# 13_LMS3_Power.net
KiCad netlist of a schematic drawn in Altium Designer
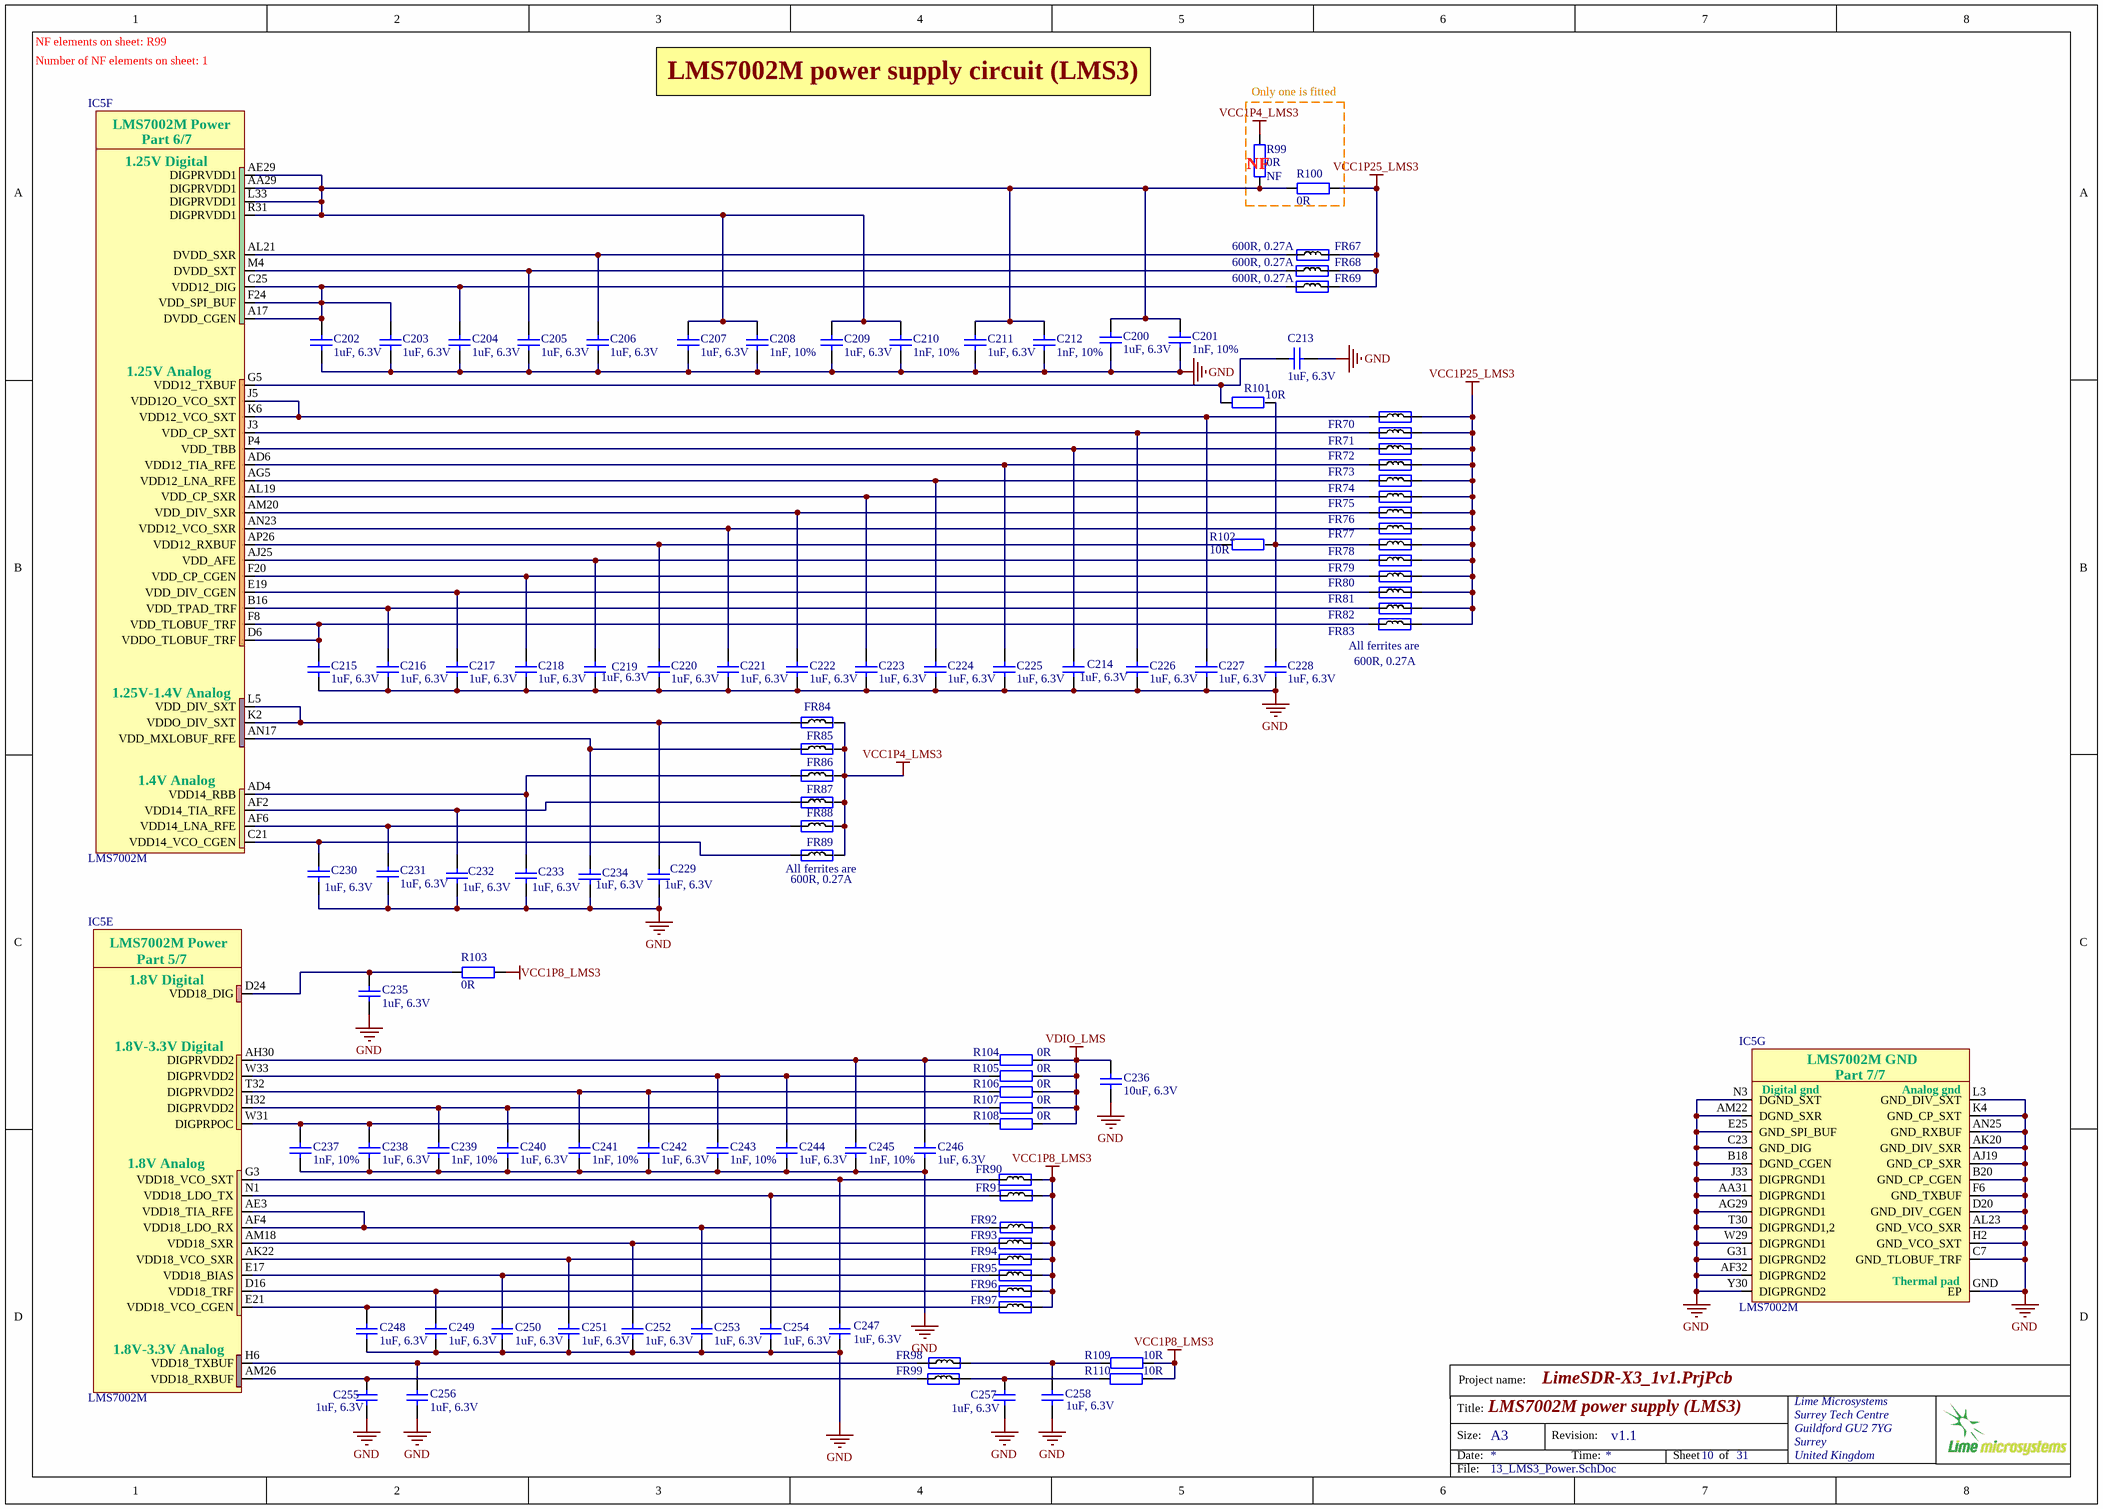
[diagram p0: 13_LMS3_Power.SchDoc]

(export (version "E")
  (design (tool "Eeschema 10.0.6"))
  (components
    (comp (ref "C200")
      (value "1uF, 6.3V")
      (footprint "CAP0201")
      (fields (field (name "TOLERANCE") "±20%") (field (name "MANUFACTURER") "TDK Corporation"))
      (libsource (lib "") (part "Cap_0402_1"))
    )
    (comp (ref "C201")
      (value "1nF, 10%")
      (footprint "CAP0201")
      (fields (field (name "TOLERANCE") "±10%") (field (name "MANUFACTURER") "TDK Corporation"))
      (libsource (lib "") (part "Cap_0402_1"))
    )
    (comp (ref "C202")
      (value "1uF, 6.3V")
      (footprint "CAP0201")
      (fields (field (name "TOLERANCE") "±20%") (field (name "MANUFACTURER") "TDK Corporation"))
      (libsource (lib "") (part "Cap_0402_2"))
    )
    (comp (ref "C203")
      (value "1uF, 6.3V")
      (footprint "CAP0201")
      (fields (field (name "TOLERANCE") "±20%") (field (name "MANUFACTURER") "TDK Corporation"))
      (libsource (lib "") (part "Cap_0402_2"))
    )
    (comp (ref "C204")
      (value "1uF, 6.3V")
      (footprint "CAP0201")
      (fields (field (name "TOLERANCE") "±20%") (field (name "MANUFACTURER") "TDK Corporation"))
      (libsource (lib "") (part "Cap_0402_2"))
    )
    (comp (ref "C205")
      (value "1uF, 6.3V")
      (footprint "CAP0201")
      (fields (field (name "TOLERANCE") "±20%") (field (name "MANUFACTURER") "TDK Corporation"))
      (libsource (lib "") (part "Cap_0402_1"))
    )
    (comp (ref "C206")
      (value "1uF, 6.3V")
      (footprint "CAP0201")
      (fields (field (name "TOLERANCE") "±20%") (field (name "MANUFACTURER") "TDK Corporation"))
      (libsource (lib "") (part "Cap_0402_2"))
    )
    (comp (ref "C207")
      (value "1uF, 6.3V")
      (footprint "CAP0201")
      (fields (field (name "TOLERANCE") "±20%") (field (name "MANUFACTURER") "TDK Corporation"))
      (libsource (lib "") (part "Cap_0402_1"))
    )
    (comp (ref "C208")
      (value "1nF, 10%")
      (footprint "CAP0201")
      (fields (field (name "TOLERANCE") "±10%") (field (name "MANUFACTURER") "TDK Corporation"))
      (libsource (lib "") (part "Cap_0402_1"))
    )
    (comp (ref "C209")
      (value "1uF, 6.3V")
      (footprint "CAP0201")
      (fields (field (name "TOLERANCE") "±20%") (field (name "MANUFACTURER") "TDK Corporation"))
      (libsource (lib "") (part "Cap_0402_1"))
    )
    (comp (ref "C210")
      (value "1nF, 10%")
      (footprint "CAP0201")
      (fields (field (name "TOLERANCE") "±10%") (field (name "MANUFACTURER") "TDK Corporation"))
      (libsource (lib "") (part "Cap_0402_1"))
    )
    (comp (ref "C211")
      (value "1uF, 6.3V")
      (footprint "CAP0201")
      (fields (field (name "TOLERANCE") "±20%") (field (name "MANUFACTURER") "TDK Corporation"))
      (libsource (lib "") (part "Cap_0402_1"))
    )
    (comp (ref "C212")
      (value "1nF, 10%")
      (footprint "CAP0201")
      (fields (field (name "TOLERANCE") "±10%") (field (name "MANUFACTURER") "TDK Corporation"))
      (libsource (lib "") (part "Cap_0402_1"))
    )
    (comp (ref "C213")
      (value "1uF, 6.3V")
      (footprint "CAP0201")
      (fields (field (name "TOLERANCE") "±20%") (field (name "MANUFACTURER") "TDK Corporation"))
      (libsource (lib "") (part "Cap_0402_4"))
    )
    (comp (ref "C214")
      (value "1uF, 6.3V")
      (footprint "CAP0201")
      (fields (field (name "TOLERANCE") "±20%") (field (name "MANUFACTURER") "TDK Corporation"))
      (libsource (lib "") (part "Cap_0402_2"))
    )
    (comp (ref "C215")
      (value "1uF, 6.3V")
      (footprint "CAP0201")
      (fields (field (name "TOLERANCE") "±20%") (field (name "MANUFACTURER") "TDK Corporation"))
      (libsource (lib "") (part "Cap_0402_2"))
    )
    (comp (ref "C216")
      (value "1uF, 6.3V")
      (footprint "CAP0201")
      (fields (field (name "TOLERANCE") "±20%") (field (name "MANUFACTURER") "TDK Corporation"))
      (libsource (lib "") (part "Cap_0402_2"))
    )
    (comp (ref "C217")
      (value "1uF, 6.3V")
      (footprint "CAP0201")
      (fields (field (name "TOLERANCE") "±20%") (field (name "MANUFACTURER") "TDK Corporation"))
      (libsource (lib "") (part "Cap_0402_2"))
    )
    (comp (ref "C218")
      (value "1uF, 6.3V")
      (footprint "CAP0201")
      (fields (field (name "TOLERANCE") "±20%") (field (name "MANUFACTURER") "TDK Corporation"))
      (libsource (lib "") (part "Cap_0402_1"))
    )
    (comp (ref "C219")
      (value "1uF, 6.3V")
      (footprint "CAP0201")
      (fields (field (name "TOLERANCE") "±20%") (field (name "MANUFACTURER") "TDK Corporation"))
      (libsource (lib "") (part "Cap_0402_2"))
    )
    (comp (ref "C220")
      (value "1uF, 6.3V")
      (footprint "CAP0201")
      (fields (field (name "TOLERANCE") "±20%") (field (name "MANUFACTURER") "TDK Corporation"))
      (libsource (lib "") (part "Cap_0402_2"))
    )
    (comp (ref "C221")
      (value "1uF, 6.3V")
      (footprint "CAP0201")
      (fields (field (name "TOLERANCE") "±20%") (field (name "MANUFACTURER") "TDK Corporation"))
      (libsource (lib "") (part "Cap_0402_2"))
    )
    (comp (ref "C222")
      (value "1uF, 6.3V")
      (footprint "CAP0201")
      (fields (field (name "TOLERANCE") "±20%") (field (name "MANUFACTURER") "TDK Corporation"))
      (libsource (lib "") (part "Cap_0402_2"))
    )
    (comp (ref "C223")
      (value "1uF, 6.3V")
      (footprint "CAP0201")
      (fields (field (name "TOLERANCE") "±20%") (field (name "MANUFACTURER") "TDK Corporation"))
      (libsource (lib "") (part "Cap_0402_2"))
    )
    (comp (ref "C224")
      (value "1uF, 6.3V")
      (footprint "CAP0201")
      (fields (field (name "TOLERANCE") "±20%") (field (name "MANUFACTURER") "TDK Corporation"))
      (libsource (lib "") (part "Cap_0402_2"))
    )
    (comp (ref "C225")
      (value "1uF, 6.3V")
      (footprint "CAP0201")
      (fields (field (name "TOLERANCE") "±20%") (field (name "MANUFACTURER") "TDK Corporation"))
      (libsource (lib "") (part "Cap_0402_1"))
    )
    (comp (ref "C226")
      (value "1uF, 6.3V")
      (footprint "CAP0201")
      (fields (field (name "TOLERANCE") "±20%") (field (name "MANUFACTURER") "TDK Corporation"))
      (libsource (lib "") (part "Cap_0402_2"))
    )
    (comp (ref "C227")
      (value "1uF, 6.3V")
      (footprint "CAP0201")
      (fields (field (name "TOLERANCE") "±20%") (field (name "MANUFACTURER") "TDK Corporation"))
      (libsource (lib "") (part "Cap_0402_1"))
    )
    (comp (ref "C228")
      (value "1uF, 6.3V")
      (footprint "CAP0201")
      (fields (field (name "TOLERANCE") "±20%") (field (name "MANUFACTURER") "TDK Corporation"))
      (libsource (lib "") (part "Cap_0402_1"))
    )
    (comp (ref "C229")
      (value "1uF, 6.3V")
      (footprint "CAP0201")
      (fields (field (name "TOLERANCE") "±20%") (field (name "MANUFACTURER") "TDK Corporation"))
      (libsource (lib "") (part "Cap_0402_2"))
    )
    (comp (ref "C230")
      (value "1uF, 6.3V")
      (footprint "CAP0201")
      (fields (field (name "TOLERANCE") "±20%") (field (name "MANUFACTURER") "TDK Corporation"))
      (libsource (lib "") (part "Cap_0402_2"))
    )
    (comp (ref "C231")
      (value "1uF, 6.3V")
      (footprint "CAP0201")
      (fields (field (name "TOLERANCE") "±20%") (field (name "MANUFACTURER") "TDK Corporation"))
      (libsource (lib "") (part "Cap_0402_2"))
    )
    (comp (ref "C232")
      (value "1uF, 6.3V")
      (footprint "CAP0201")
      (fields (field (name "TOLERANCE") "±20%") (field (name "MANUFACTURER") "TDK Corporation"))
      (libsource (lib "") (part "Cap_0402_3"))
    )
    (comp (ref "C233")
      (value "1uF, 6.3V")
      (footprint "CAP0201")
      (fields (field (name "TOLERANCE") "±20%") (field (name "MANUFACTURER") "TDK Corporation"))
      (libsource (lib "") (part "Cap_0402_3"))
    )
    (comp (ref "C234")
      (value "1uF, 6.3V")
      (footprint "CAP0201")
      (fields (field (name "TOLERANCE") "±20%") (field (name "MANUFACTURER") "TDK Corporation"))
      (libsource (lib "") (part "Cap_0402_2"))
    )
    (comp (ref "C235")
      (value "1uF, 6.3V")
      (footprint "CAP0201")
      (fields (field (name "TOLERANCE") "±20%") (field (name "MANUFACTURER") "TDK Corporation"))
      (libsource (lib "LimeMicroAltiumLib_schLib") (part "Cap_0402"))
    )
    (comp (ref "C236")
      (value "10uF, 6.3V")
      (footprint "CAP0603")
      (fields (field (name "TOLERANCE") "±20%") (field (name "MANUFACTURER") "Yageo"))
      (libsource (lib "LimeFPGAboard_schLib") (part "Cap_0603"))
    )
    (comp (ref "C237")
      (value "1nF, 10%")
      (footprint "CAP0201")
      (fields (field (name "TOLERANCE") "±10%") (field (name "MANUFACTURER") "TDK Corporation"))
      (libsource (lib "LimeMicroAltiumLib_schLib") (part "Cap_0402"))
    )
    (comp (ref "C238")
      (value "1uF, 6.3V")
      (footprint "CAP0201")
      (fields (field (name "TOLERANCE") "±20%") (field (name "MANUFACTURER") "TDK Corporation"))
      (libsource (lib "LimeMicroAltiumLib_schLib") (part "Cap_0402"))
    )
    (comp (ref "C239")
      (value "1nF, 10%")
      (footprint "CAP0201")
      (fields (field (name "TOLERANCE") "±10%") (field (name "MANUFACTURER") "TDK Corporation"))
      (libsource (lib "LimeMicroAltiumLib_schLib") (part "Cap_0402"))
    )
    (comp (ref "C240")
      (value "1uF, 6.3V")
      (footprint "CAP0201")
      (fields (field (name "TOLERANCE") "±20%") (field (name "MANUFACTURER") "TDK Corporation"))
      (libsource (lib "LimeMicroAltiumLib_schLib") (part "Cap_0402"))
    )
    (comp (ref "C241")
      (value "1nF, 10%")
      (footprint "CAP0201")
      (fields (field (name "TOLERANCE") "±10%") (field (name "MANUFACTURER") "TDK Corporation"))
      (libsource (lib "LimeMicroAltiumLib_schLib") (part "Cap_0402"))
    )
    (comp (ref "C242")
      (value "1uF, 6.3V")
      (footprint "CAP0201")
      (fields (field (name "TOLERANCE") "±20%") (field (name "MANUFACTURER") "TDK Corporation"))
      (libsource (lib "LimeMicroAltiumLib_schLib") (part "Cap_0402"))
    )
    (comp (ref "C243")
      (value "1nF, 10%")
      (footprint "CAP0201")
      (fields (field (name "TOLERANCE") "±10%") (field (name "MANUFACTURER") "TDK Corporation"))
      (libsource (lib "LimeMicroAltiumLib_schLib") (part "Cap_0402"))
    )
    (comp (ref "C244")
      (value "1uF, 6.3V")
      (footprint "CAP0201")
      (fields (field (name "TOLERANCE") "±20%") (field (name "MANUFACTURER") "TDK Corporation"))
      (libsource (lib "LimeMicroAltiumLib_schLib") (part "Cap_0402"))
    )
    (comp (ref "C245")
      (value "1nF, 10%")
      (footprint "CAP0201")
      (fields (field (name "TOLERANCE") "±10%") (field (name "MANUFACTURER") "TDK Corporation"))
      (libsource (lib "LimeMicroAltiumLib_schLib") (part "Cap_0402"))
    )
    (comp (ref "C246")
      (value "1uF, 6.3V")
      (footprint "CAP0201")
      (fields (field (name "TOLERANCE") "±20%") (field (name "MANUFACTURER") "TDK Corporation"))
      (libsource (lib "LimeMicroAltiumLib_schLib") (part "Cap_0402"))
    )
    (comp (ref "C247")
      (value "1uF, 6.3V")
      (footprint "CAP0201")
      (fields (field (name "TOLERANCE") "±20%") (field (name "MANUFACTURER") "TDK Corporation"))
      (libsource (lib "LimeMicroAltiumLib_schLib") (part "Cap_0402"))
    )
    (comp (ref "C248")
      (value "1uF, 6.3V")
      (footprint "CAP0201")
      (fields (field (name "TOLERANCE") "±20%") (field (name "MANUFACTURER") "TDK Corporation"))
      (libsource (lib "LimeMicroAltiumLib_schLib") (part "Cap_0402"))
    )
    (comp (ref "C249")
      (value "1uF, 6.3V")
      (footprint "CAP0201")
      (fields (field (name "TOLERANCE") "±20%") (field (name "MANUFACTURER") "TDK Corporation"))
      (libsource (lib "LimeMicroAltiumLib_schLib") (part "Cap_0402"))
    )
    (comp (ref "C250")
      (value "1uF, 6.3V")
      (footprint "CAP0201")
      (fields (field (name "TOLERANCE") "±20%") (field (name "MANUFACTURER") "TDK Corporation"))
      (libsource (lib "LimeMicroAltiumLib_schLib") (part "Cap_0402"))
    )
    (comp (ref "C251")
      (value "1uF, 6.3V")
      (footprint "CAP0201")
      (fields (field (name "TOLERANCE") "±20%") (field (name "MANUFACTURER") "TDK Corporation"))
      (libsource (lib "LimeMicroAltiumLib_schLib") (part "Cap_0402"))
    )
    (comp (ref "C252")
      (value "1uF, 6.3V")
      (footprint "CAP0201")
      (fields (field (name "TOLERANCE") "±20%") (field (name "MANUFACTURER") "TDK Corporation"))
      (libsource (lib "LimeMicroAltiumLib_schLib") (part "Cap_0402"))
    )
    (comp (ref "C253")
      (value "1uF, 6.3V")
      (footprint "CAP0201")
      (fields (field (name "TOLERANCE") "±20%") (field (name "MANUFACTURER") "TDK Corporation"))
      (libsource (lib "LimeMicroAltiumLib_schLib") (part "Cap_0402"))
    )
    (comp (ref "C254")
      (value "1uF, 6.3V")
      (footprint "CAP0201")
      (fields (field (name "TOLERANCE") "±20%") (field (name "MANUFACTURER") "TDK Corporation"))
      (libsource (lib "LimeMicroAltiumLib_schLib") (part "Cap_0402"))
    )
    (comp (ref "C255")
      (value "1uF, 6.3V")
      (footprint "CAP0201")
      (fields (field (name "TOLERANCE") "±20%") (field (name "MANUFACTURER") "TDK Corporation"))
      (libsource (lib "LimeMicroAltiumLib_schLib") (part "Cap_0402"))
    )
    (comp (ref "C256")
      (value "1uF, 6.3V")
      (footprint "CAP0201")
      (fields (field (name "TOLERANCE") "±20%") (field (name "MANUFACTURER") "TDK Corporation"))
      (libsource (lib "LimeMicroAltiumLib_schLib") (part "Cap_0402"))
    )
    (comp (ref "C257")
      (value "1uF, 6.3V")
      (footprint "CAP0201")
      (fields (field (name "TOLERANCE") "±20%") (field (name "MANUFACTURER") "TDK Corporation"))
      (libsource (lib "LimeMicroAltiumLib_schLib") (part "Cap_0402"))
    )
    (comp (ref "C258")
      (value "1uF, 6.3V")
      (footprint "CAP0201")
      (fields (field (name "TOLERANCE") "±20%") (field (name "MANUFACTURER") "TDK Corporation"))
      (libsource (lib "LimeMicroAltiumLib_schLib") (part "Cap_0402"))
    )
    (comp (ref "FR67")
      (value "600R, 0.27A")
      (footprint "RES0201")
      (fields (field (name "MANUFACTURER") "Taiyo Yuden"))
      (libsource (lib "") (part "Ferrite_2"))
    )
    (comp (ref "FR68")
      (value "600R, 0.27A")
      (footprint "RES0201")
      (fields (field (name "MANUFACTURER") "Taiyo Yuden"))
      (libsource (lib "") (part "Ferrite_1"))
    )
    (comp (ref "FR69")
      (value "600R, 0.27A")
      (footprint "RES0201")
      (fields (field (name "MANUFACTURER") "Taiyo Yuden"))
      (libsource (lib "") (part "Ferrite_1"))
    )
    (comp (ref "FR70")
      (value "600R, 0.27A")
      (footprint "RES0201")
      (fields (field (name "MANUFACTURER") "Taiyo Yuden"))
      (libsource (lib "") (part "Ferrite_2"))
    )
    (comp (ref "FR71")
      (value "600R, 0.27A")
      (footprint "RES0201")
      (fields (field (name "MANUFACTURER") "Taiyo Yuden"))
      (libsource (lib "") (part "Ferrite_2"))
    )
    (comp (ref "FR72")
      (value "600R, 0.27A")
      (footprint "RES0201")
      (fields (field (name "MANUFACTURER") "Taiyo Yuden"))
      (libsource (lib "") (part "Ferrite_2"))
    )
    (comp (ref "FR73")
      (value "600R, 0.27A")
      (footprint "RES0201")
      (fields (field (name "MANUFACTURER") "Taiyo Yuden"))
      (libsource (lib "") (part "Ferrite_2"))
    )
    (comp (ref "FR74")
      (value "600R, 0.27A")
      (footprint "RES0201")
      (fields (field (name "MANUFACTURER") "Taiyo Yuden"))
      (libsource (lib "") (part "Ferrite_2"))
    )
    (comp (ref "FR75")
      (value "600R, 0.27A")
      (footprint "RES0201")
      (fields (field (name "MANUFACTURER") "Taiyo Yuden"))
      (libsource (lib "") (part "Ferrite_2"))
    )
    (comp (ref "FR76")
      (value "600R, 0.27A")
      (footprint "RES0201")
      (fields (field (name "MANUFACTURER") "Taiyo Yuden"))
      (libsource (lib "") (part "Ferrite_2"))
    )
    (comp (ref "FR77")
      (value "600R, 0.27A")
      (footprint "RES0201")
      (fields (field (name "MANUFACTURER") "Taiyo Yuden"))
      (libsource (lib "") (part "Ferrite_2"))
    )
    (comp (ref "FR78")
      (value "600R, 0.27A")
      (footprint "RES0201")
      (fields (field (name "MANUFACTURER") "Taiyo Yuden"))
      (libsource (lib "") (part "Ferrite_2"))
    )
    (comp (ref "FR79")
      (value "600R, 0.27A")
      (footprint "RES0201")
      (fields (field (name "MANUFACTURER") "Taiyo Yuden"))
      (libsource (lib "") (part "Ferrite_2"))
    )
    (comp (ref "FR80")
      (value "600R, 0.27A")
      (footprint "RES0201")
      (fields (field (name "MANUFACTURER") "Taiyo Yuden"))
      (libsource (lib "") (part "Ferrite_2"))
    )
    (comp (ref "FR81")
      (value "600R, 0.27A")
      (footprint "RES0201")
      (fields (field (name "MANUFACTURER") "Taiyo Yuden"))
      (libsource (lib "") (part "Ferrite_2"))
    )
    (comp (ref "FR82")
      (value "600R, 0.27A")
      (footprint "RES0201")
      (fields (field (name "MANUFACTURER") "Taiyo Yuden"))
      (libsource (lib "") (part "Ferrite_2"))
    )
    (comp (ref "FR83")
      (value "600R, 0.27A")
      (footprint "RES0201")
      (fields (field (name "MANUFACTURER") "Taiyo Yuden"))
      (libsource (lib "") (part "Ferrite_1"))
    )
    (comp (ref "FR84")
      (value "600R, 0.27A")
      (footprint "RES0201")
      (fields (field (name "MANUFACTURER") "Taiyo Yuden"))
      (libsource (lib "") (part "Ferrite_1"))
    )
    (comp (ref "FR85")
      (value "600R, 0.27A")
      (footprint "RES0201")
      (fields (field (name "MANUFACTURER") "Taiyo Yuden"))
      (libsource (lib "") (part "Ferrite_1"))
    )
    (comp (ref "FR86")
      (value "600R, 0.27A")
      (footprint "RES0201")
      (fields (field (name "MANUFACTURER") "Taiyo Yuden"))
      (libsource (lib "") (part "Ferrite_1"))
    )
    (comp (ref "FR87")
      (value "600R, 0.27A")
      (footprint "RES0201")
      (fields (field (name "MANUFACTURER") "Taiyo Yuden"))
      (libsource (lib "") (part "Ferrite_1"))
    )
    (comp (ref "FR88")
      (value "600R, 0.27A")
      (footprint "RES0201")
      (fields (field (name "MANUFACTURER") "Taiyo Yuden"))
      (libsource (lib "") (part "Ferrite_1"))
    )
    (comp (ref "FR89")
      (value "600R, 0.27A")
      (footprint "RES0201")
      (fields (field (name "MANUFACTURER") "Taiyo Yuden"))
      (libsource (lib "") (part "Ferrite_1"))
    )
    (comp (ref "FR90")
      (value "600R, 0.27A")
      (footprint "RES0201")
      (fields (field (name "MANUFACTURER") "Taiyo Yuden"))
      (libsource (lib "") (part "Ferrite_1"))
    )
    (comp (ref "FR91")
      (value "600R, 0.27A")
      (footprint "RES0201")
      (fields (field (name "MANUFACTURER") "Taiyo Yuden"))
      (libsource (lib "LimeMicroAltiumLib_schLib") (part "Ferrite"))
    )
    (comp (ref "FR92")
      (value "600R, 0.27A")
      (footprint "RES0201")
      (fields (field (name "MANUFACTURER") "Taiyo Yuden"))
      (libsource (lib "LimeMicroAltiumLib_schLib") (part "Ferrite"))
    )
    (comp (ref "FR93")
      (value "600R, 0.27A")
      (footprint "RES0201")
      (fields (field (name "MANUFACTURER") "Taiyo Yuden"))
      (libsource (lib "") (part "Ferrite_1"))
    )
    (comp (ref "FR94")
      (value "600R, 0.27A")
      (footprint "RES0201")
      (fields (field (name "MANUFACTURER") "Taiyo Yuden"))
      (libsource (lib "") (part "Ferrite_1"))
    )
    (comp (ref "FR95")
      (value "600R, 0.27A")
      (footprint "RES0201")
      (fields (field (name "MANUFACTURER") "Taiyo Yuden"))
      (libsource (lib "") (part "Ferrite_1"))
    )
    (comp (ref "FR96")
      (value "600R, 0.27A")
      (footprint "RES0201")
      (fields (field (name "MANUFACTURER") "Taiyo Yuden"))
      (libsource (lib "") (part "Ferrite_1"))
    )
    (comp (ref "FR97")
      (value "600R, 0.27A")
      (footprint "RES0201")
      (fields (field (name "MANUFACTURER") "Taiyo Yuden"))
      (libsource (lib "") (part "Ferrite_1"))
    )
    (comp (ref "FR98")
      (value "600R, 0.27A")
      (footprint "RES0201")
      (fields (field (name "MANUFACTURER") "Taiyo Yuden"))
      (libsource (lib "LimeMicroAltiumLib_schLib") (part "Ferrite"))
    )
    (comp (ref "FR99")
      (value "600R, 0.27A")
      (footprint "RES0201")
      (fields (field (name "MANUFACTURER") "Taiyo Yuden"))
      (libsource (lib "") (part "Ferrite_1"))
    )
    (comp (ref "IC5")
      (value "LMS7002M")
      (footprint "LMS7002M_v5")
      (description "Schematic symbol revision 4. Default footprint - 0.31mm pad")
      (fields (field (name "MANUFACTURER") "Lime Microsystems"))
      (libsource (lib "LimeMicroAltiumLib_schLib_r04") (part "LMS7002Mr4"))
    )
    (comp (ref "R99")
      (value "0R")
      (footprint "RES0402")
      (fields
        (field (name "ASSEMBLY INFO") "NF")
        (field (name "MANUFACTURER") "Yageo")
        (field (name "TOLERANCE") "Jumper")
      )
      (libsource (lib "LimeMicroAltiumLib_schLib") (part "Res_0402"))
    )
    (comp (ref "R100")
      (value "0R")
      (footprint "RES0402")
      (fields (field (name "MANUFACTURER") "Yageo") (field (name "TOLERANCE") "Jumper"))
      (libsource (lib "") (part "Res_0402_1"))
    )
    (comp (ref "R101")
      (value "10R")
      (footprint "RES0201")
      (fields
        (field (name "MANUFACTURER") "Panasonic Electronic Components")
        (field (name "TOLERANCE") "±1%")
      )
      (libsource (lib "LimeMicroAltiumLib_schLib") (part "Res_0402"))
    )
    (comp (ref "R102")
      (value "10R")
      (footprint "RES0201")
      (fields
        (field (name "MANUFACTURER") "Panasonic Electronic Components")
        (field (name "TOLERANCE") "±1%")
      )
      (libsource (lib "LimeMicroAltiumLib_schLib") (part "Res_0402"))
    )
    (comp (ref "R103")
      (value "0R")
      (footprint "RES0201")
      (fields (field (name "MANUFACTURER") "Rohm Semiconductor") (field (name "TOLERANCE") "Jumper"))
      (libsource (lib "LimeMicroAltiumLib_schLib") (part "Res_0402"))
    )
    (comp (ref "R104")
      (value "0R")
      (footprint "RES0402")
      (fields (field (name "MANUFACTURER") "Yageo") (field (name "TOLERANCE") "Jumper"))
      (libsource (lib "LimeMicroAltiumLib_schLib") (part "Res_0402"))
    )
    (comp (ref "R105")
      (value "0R")
      (footprint "RES0402")
      (fields (field (name "MANUFACTURER") "Yageo") (field (name "TOLERANCE") "Jumper"))
      (libsource (lib "LimeMicroAltiumLib_schLib") (part "Res_0402"))
    )
    (comp (ref "R106")
      (value "0R")
      (footprint "RES0402")
      (fields (field (name "MANUFACTURER") "Yageo") (field (name "TOLERANCE") "Jumper"))
      (libsource (lib "LimeMicroAltiumLib_schLib") (part "Res_0402"))
    )
    (comp (ref "R107")
      (value "0R")
      (footprint "RES0402")
      (fields (field (name "MANUFACTURER") "Yageo") (field (name "TOLERANCE") "Jumper"))
      (libsource (lib "LimeMicroAltiumLib_schLib") (part "Res_0402"))
    )
    (comp (ref "R108")
      (value "0R")
      (footprint "RES0402")
      (fields (field (name "MANUFACTURER") "Yageo") (field (name "TOLERANCE") "Jumper"))
      (libsource (lib "LimeMicroAltiumLib_schLib") (part "Res_0402"))
    )
    (comp (ref "R109")
      (value "10R")
      (footprint "RES0201")
      (fields
        (field (name "MANUFACTURER") "Panasonic Electronic Components")
        (field (name "TOLERANCE") "±1%")
      )
      (libsource (lib "LimeMicroAltiumLib_schLib") (part "Res_0402"))
    )
    (comp (ref "R110")
      (value "10R")
      (footprint "RES0201")
      (fields
        (field (name "MANUFACTURER") "Panasonic Electronic Components")
        (field (name "TOLERANCE") "±1%")
      )
      (libsource (lib "LimeMicroAltiumLib_schLib") (part "Res_0402"))
    )
  )
  (nets
    (net (code "1") (name "GND") (class "Default")
      (node (ref "C200") (pin "2") (pinfunction "2_2") (pintype "passive"))
      (node (ref "C201") (pin "2") (pinfunction "2_2") (pintype "passive"))
      (node (ref "C202") (pin "2") (pinfunction "2_2") (pintype "passive"))
      (node (ref "C203") (pin "2") (pinfunction "2_2") (pintype "passive"))
      (node (ref "C204") (pin "2") (pinfunction "2_2") (pintype "passive"))
      (node (ref "C205") (pin "1") (pinfunction "1_1") (pintype "passive"))
      (node (ref "C206") (pin "2") (pinfunction "2_2") (pintype "passive"))
      (node (ref "C207") (pin "2") (pinfunction "2_2") (pintype "passive"))
      (node (ref "C208") (pin "2") (pinfunction "2_2") (pintype "passive"))
      (node (ref "C209") (pin "2") (pinfunction "2_2") (pintype "passive"))
      (node (ref "C210") (pin "2") (pinfunction "2_2") (pintype "passive"))
      (node (ref "C211") (pin "2") (pinfunction "2_2") (pintype "passive"))
      (node (ref "C212") (pin "2") (pinfunction "2_2") (pintype "passive"))
      (node (ref "C213") (pin "2") (pinfunction "2_2") (pintype "passive"))
      (node (ref "C214") (pin "2") (pinfunction "2_2") (pintype "passive"))
      (node (ref "C215") (pin "2") (pinfunction "2_2") (pintype "passive"))
      (node (ref "C216") (pin "2") (pinfunction "2_2") (pintype "passive"))
      (node (ref "C217") (pin "2") (pinfunction "2_2") (pintype "passive"))
      (node (ref "C218") (pin "1") (pinfunction "1_1") (pintype "passive"))
      (node (ref "C219") (pin "2") (pinfunction "2_2") (pintype "passive"))
      (node (ref "C220") (pin "2") (pinfunction "2_2") (pintype "passive"))
      (node (ref "C221") (pin "2") (pinfunction "2_2") (pintype "passive"))
      (node (ref "C222") (pin "2") (pinfunction "2_2") (pintype "passive"))
      (node (ref "C223") (pin "2") (pinfunction "2_2") (pintype "passive"))
      (node (ref "C224") (pin "2") (pinfunction "2_2") (pintype "passive"))
      (node (ref "C225") (pin "1") (pinfunction "1_1") (pintype "passive"))
      (node (ref "C226") (pin "2") (pinfunction "2_2") (pintype "passive"))
      (node (ref "C227") (pin "1") (pinfunction "1_1") (pintype "passive"))
      (node (ref "C228") (pin "1") (pinfunction "1_1") (pintype "passive"))
      (node (ref "C229") (pin "2") (pinfunction "2_2") (pintype "passive"))
      (node (ref "C230") (pin "2") (pinfunction "2_2") (pintype "passive"))
      (node (ref "C231") (pin "2") (pinfunction "2_2") (pintype "passive"))
      (node (ref "C232") (pin "2") (pinfunction "2_2") (pintype "passive"))
      (node (ref "C233") (pin "2") (pinfunction "2_2") (pintype "passive"))
      (node (ref "C234") (pin "2") (pinfunction "2_2") (pintype "passive"))
      (node (ref "C235") (pin "2") (pinfunction "2_2") (pintype "passive"))
      (node (ref "C236") (pin "1") (pinfunction "1_1") (pintype "passive"))
      (node (ref "C237") (pin "2") (pinfunction "2_2") (pintype "passive"))
      (node (ref "C238") (pin "2") (pinfunction "2_2") (pintype "passive"))
      (node (ref "C239") (pin "2") (pinfunction "2_2") (pintype "passive"))
      (node (ref "C240") (pin "2") (pinfunction "2_2") (pintype "passive"))
      (node (ref "C241") (pin "2") (pinfunction "2_2") (pintype "passive"))
      (node (ref "C242") (pin "2") (pinfunction "2_2") (pintype "passive"))
      (node (ref "C243") (pin "2") (pinfunction "2_2") (pintype "passive"))
      (node (ref "C244") (pin "2") (pinfunction "2_2") (pintype "passive"))
      (node (ref "C245") (pin "2") (pinfunction "2_2") (pintype "passive"))
      (node (ref "C246") (pin "2") (pinfunction "2_2") (pintype "passive"))
      (node (ref "C247") (pin "2") (pinfunction "2_2") (pintype "passive"))
      (node (ref "C248") (pin "2") (pinfunction "2_2") (pintype "passive"))
      (node (ref "C249") (pin "2") (pinfunction "2_2") (pintype "passive"))
      (node (ref "C250") (pin "2") (pinfunction "2_2") (pintype "passive"))
      (node (ref "C251") (pin "2") (pinfunction "2_2") (pintype "passive"))
      (node (ref "C252") (pin "2") (pinfunction "2_2") (pintype "passive"))
      (node (ref "C253") (pin "2") (pinfunction "2_2") (pintype "passive"))
      (node (ref "C254") (pin "2") (pinfunction "2_2") (pintype "passive"))
      (node (ref "C255") (pin "2") (pinfunction "2_2") (pintype "passive"))
      (node (ref "C256") (pin "2") (pinfunction "2_2") (pintype "passive"))
      (node (ref "C257") (pin "2") (pinfunction "2_2") (pintype "passive"))
      (node (ref "C258") (pin "2") (pinfunction "2_2") (pintype "passive"))
      (node (ref "IC5") (pin "AA31") (pinfunction "DIGPRGND1_AA31") (pintype "passive"))
      (node (ref "IC5") (pin "AF32") (pinfunction "DIGPRGND2_AF32") (pintype "passive"))
      (node (ref "IC5") (pin "AG29") (pinfunction "DIGPRGND1_AG29") (pintype "passive"))
      (node (ref "IC5") (pin "AJ19") (pinfunction "GND_CP_SXR_AJ19") (pintype "passive"))
      (node (ref "IC5") (pin "AK20") (pinfunction "GND_DIV_SXR_AK20") (pintype "passive"))
      (node (ref "IC5") (pin "AL23") (pinfunction "GND_VCO_SXR_AL23") (pintype "passive"))
      (node (ref "IC5") (pin "AM22") (pinfunction "DGND_SXR_AM22") (pintype "passive"))
      (node (ref "IC5") (pin "AN25") (pinfunction "GND_RXBUF_AN25") (pintype "passive"))
      (node (ref "IC5") (pin "B18") (pinfunction "DGND_CGEN_B18") (pintype "passive"))
      (node (ref "IC5") (pin "B20") (pinfunction "GND_CP_CGEN_B20") (pintype "passive"))
      (node (ref "IC5") (pin "C23") (pinfunction "GND_DIG_C23") (pintype "passive"))
      (node (ref "IC5") (pin "C7") (pinfunction "GND_TLOBUF_TRF_C7") (pintype "passive"))
      (node (ref "IC5") (pin "D20") (pinfunction "GND_DIV_CGEN_D20") (pintype "passive"))
      (node (ref "IC5") (pin "E25") (pinfunction "GND_SPI_BUF_E25") (pintype "passive"))
      (node (ref "IC5") (pin "F6") (pinfunction "GND_TXBUF_F6") (pintype "passive"))
      (node (ref "IC5") (pin "G31") (pinfunction "DIGPRGND2_G31") (pintype "passive"))
      (node (ref "IC5") (pin "GND") (pinfunction "EP_GND") (pintype "passive"))
      (node (ref "IC5") (pin "H2") (pinfunction "GND_VCO_SXT_H2") (pintype "passive"))
      (node (ref "IC5") (pin "J33") (pinfunction "DIGPRGND1_J33") (pintype "passive"))
      (node (ref "IC5") (pin "K4") (pinfunction "GND_CP_SXT_K4") (pintype "passive"))
      (node (ref "IC5") (pin "L3") (pinfunction "GND_DIV_SXT_L3") (pintype "passive"))
      (node (ref "IC5") (pin "N3") (pinfunction "DGND_SXT_N3") (pintype "passive"))
      (node (ref "IC5") (pin "T30") (pinfunction "DIGPRGND1,2_T30") (pintype "passive"))
      (node (ref "IC5") (pin "W29") (pinfunction "DIGPRGND1_W29") (pintype "passive"))
      (node (ref "IC5") (pin "Y30") (pinfunction "DIGPRGND2_Y30") (pintype "passive"))
    )
    (net (code "2") (name "Net-(C200-Pad1)") (class "Default")
      (node (ref "C200") (pin "1") (pinfunction "1_1") (pintype "passive"))
      (node (ref "C201") (pin "1") (pinfunction "1_1") (pintype "passive"))
      (node (ref "C207") (pin "1") (pinfunction "1_1") (pintype "passive"))
      (node (ref "C208") (pin "1") (pinfunction "1_1") (pintype "passive"))
      (node (ref "C209") (pin "1") (pinfunction "1_1") (pintype "passive"))
      (node (ref "C210") (pin "1") (pinfunction "1_1") (pintype "passive"))
      (node (ref "C211") (pin "1") (pinfunction "1_1") (pintype "passive"))
      (node (ref "C212") (pin "1") (pinfunction "1_1") (pintype "passive"))
      (node (ref "IC5") (pin "AA29") (pinfunction "DIGPRVDD1_AA29") (pintype "power_in"))
      (node (ref "IC5") (pin "AE29") (pinfunction "DIGPRVDD1_AE29") (pintype "power_in"))
      (node (ref "IC5") (pin "L33") (pinfunction "DIGPRVDD1_L33") (pintype "power_in"))
      (node (ref "IC5") (pin "R31") (pinfunction "DIGPRVDD1_R31") (pintype "power_in"))
      (node (ref "R100") (pin "2") (pinfunction "2_2") (pintype "passive"))
      (node (ref "R99") (pin "2") (pinfunction "2_2") (pintype "passive"))
    )
    (net (code "3") (name "Net-(C228-Pad2)") (class "Default")
      (node (ref "C228") (pin "2") (pinfunction "2_2") (pintype "passive"))
      (node (ref "FR78") (pin "1") (pinfunction "1_1") (pintype "passive"))
      (node (ref "R101") (pin "2") (pinfunction "2_2") (pintype "passive"))
      (node (ref "R102") (pin "2") (pinfunction "2_2") (pintype "passive"))
    )
    (net (code "4") (name "Net-(C239-Pad1)") (class "Default")
      (node (ref "C239") (pin "1") (pinfunction "1_1") (pintype "passive"))
      (node (ref "C240") (pin "1") (pinfunction "1_1") (pintype "passive"))
      (node (ref "IC5") (pin "H32") (pinfunction "DIGPRVDD2_H32") (pintype "power_in"))
      (node (ref "R107") (pin "2") (pinfunction "2_2") (pintype "passive"))
    )
    (net (code "5") (name "Net-(C241-Pad1)") (class "Default")
      (node (ref "C241") (pin "1") (pinfunction "1_1") (pintype "passive"))
      (node (ref "C242") (pin "1") (pinfunction "1_1") (pintype "passive"))
      (node (ref "IC5") (pin "T32") (pinfunction "DIGPRVDD2_T32") (pintype "power_in"))
      (node (ref "R106") (pin "2") (pinfunction "2_2") (pintype "passive"))
    )
    (net (code "6") (name "Net-(C243-Pad1)") (class "Default")
      (node (ref "C243") (pin "1") (pinfunction "1_1") (pintype "passive"))
      (node (ref "C244") (pin "1") (pinfunction "1_1") (pintype "passive"))
      (node (ref "IC5") (pin "W33") (pinfunction "DIGPRVDD2_W33") (pintype "power_in"))
      (node (ref "R105") (pin "2") (pinfunction "2_2") (pintype "passive"))
    )
    (net (code "7") (name "Net-(C245-Pad1)") (class "Default")
      (node (ref "C245") (pin "1") (pinfunction "1_1") (pintype "passive"))
      (node (ref "C246") (pin "1") (pinfunction "1_1") (pintype "passive"))
      (node (ref "IC5") (pin "AH30") (pinfunction "DIGPRVDD2_AH30") (pintype "power_in"))
      (node (ref "R104") (pin "2") (pinfunction "2_2") (pintype "passive"))
    )
    (net (code "8") (name "Net-(C257-Pad1)") (class "Default")
      (node (ref "C257") (pin "1") (pinfunction "1_1") (pintype "passive"))
      (node (ref "FR99") (pin "2") (pinfunction "2_2") (pintype "passive"))
      (node (ref "R110") (pin "2") (pinfunction "2_2") (pintype "passive"))
    )
    (net (code "9") (name "Net-(C258-Pad1)") (class "Default")
      (node (ref "C258") (pin "1") (pinfunction "1_1") (pintype "passive"))
      (node (ref "FR98") (pin "1") (pinfunction "1_1") (pintype "passive"))
      (node (ref "R109") (pin "1") (pinfunction "1_1") (pintype "passive"))
    )
    (net (code "10") (name "Net-(IC5E-DIGPRPOC)") (class "Default")
      (node (ref "C237") (pin "1") (pinfunction "1_1") (pintype "passive"))
      (node (ref "C238") (pin "1") (pinfunction "1_1") (pintype "passive"))
      (node (ref "IC5") (pin "W31") (pinfunction "DIGPRPOC_W31") (pintype "power_in"))
      (node (ref "R108") (pin "2") (pinfunction "2_2") (pintype "passive"))
    )
    (net (code "11") (name "Net-(IC5E-VDD18_BIAS)") (class "Default")
      (node (ref "C250") (pin "1") (pinfunction "1_1") (pintype "passive"))
      (node (ref "FR95") (pin "1") (pinfunction "1_1") (pintype "passive"))
      (node (ref "IC5") (pin "E17") (pinfunction "VDD18_BIAS_E17") (pintype "power_in"))
    )
    (net (code "12") (name "Net-(IC5E-VDD18_DIG)") (class "Default")
      (node (ref "C235") (pin "1") (pinfunction "1_1") (pintype "passive"))
      (node (ref "IC5") (pin "D24") (pinfunction "VDD18_DIG_D24") (pintype "power_in"))
      (node (ref "R103") (pin "1") (pinfunction "1_1") (pintype "passive"))
    )
    (net (code "13") (name "Net-(IC5E-VDD18_LDO_RX)") (class "Default")
      (node (ref "C253") (pin "1") (pinfunction "1_1") (pintype "passive"))
      (node (ref "FR92") (pin "2") (pinfunction "2_2") (pintype "passive"))
      (node (ref "IC5") (pin "AE3") (pinfunction "VDD18_TIA_RFE_AE3") (pintype "power_in"))
      (node (ref "IC5") (pin "AF4") (pinfunction "VDD18_LDO_RX_AF4") (pintype "power_in"))
    )
    (net (code "14") (name "Net-(IC5E-VDD18_LDO_TX)") (class "Default")
      (node (ref "C254") (pin "1") (pinfunction "1_1") (pintype "passive"))
      (node (ref "FR91") (pin "2") (pinfunction "2_2") (pintype "passive"))
      (node (ref "IC5") (pin "N1") (pinfunction "VDD18_LDO_TX_N1") (pintype "power_in"))
    )
    (net (code "15") (name "Net-(IC5E-VDD18_RXBUF)") (class "Default")
      (node (ref "C255") (pin "1") (pinfunction "1_1") (pintype "passive"))
      (node (ref "FR99") (pin "1") (pinfunction "1_1") (pintype "passive"))
      (node (ref "IC5") (pin "AM26") (pinfunction "VDD18_RXBUF_AM26") (pintype "power_in"))
    )
    (net (code "16") (name "Net-(IC5E-VDD18_SXR)") (class "Default")
      (node (ref "C252") (pin "1") (pinfunction "1_1") (pintype "passive"))
      (node (ref "FR93") (pin "1") (pinfunction "1_1") (pintype "passive"))
      (node (ref "IC5") (pin "AM18") (pinfunction "VDD18_SXR_AM18") (pintype "power_in"))
    )
    (net (code "17") (name "Net-(IC5E-VDD18_TRF)") (class "Default")
      (node (ref "C249") (pin "1") (pinfunction "1_1") (pintype "passive"))
      (node (ref "FR96") (pin "1") (pinfunction "1_1") (pintype "passive"))
      (node (ref "IC5") (pin "D16") (pinfunction "VDD18_TRF_D16") (pintype "power_in"))
    )
    (net (code "18") (name "Net-(IC5E-VDD18_TXBUF)") (class "Default")
      (node (ref "C256") (pin "1") (pinfunction "1_1") (pintype "passive"))
      (node (ref "FR98") (pin "2") (pinfunction "2_2") (pintype "passive"))
      (node (ref "IC5") (pin "H6") (pinfunction "VDD18_TXBUF_H6") (pintype "power_in"))
    )
    (net (code "19") (name "Net-(IC5E-VDD18_VCO_CGEN)") (class "Default")
      (node (ref "C248") (pin "1") (pinfunction "1_1") (pintype "passive"))
      (node (ref "FR97") (pin "1") (pinfunction "1_1") (pintype "passive"))
      (node (ref "IC5") (pin "E21") (pinfunction "VDD18_VCO_CGEN_E21") (pintype "power_in"))
    )
    (net (code "20") (name "Net-(IC5E-VDD18_VCO_SXR)") (class "Default")
      (node (ref "C251") (pin "1") (pinfunction "1_1") (pintype "passive"))
      (node (ref "FR94") (pin "1") (pinfunction "1_1") (pintype "passive"))
      (node (ref "IC5") (pin "AK22") (pinfunction "VDD18_VCO_SXR_AK22") (pintype "power_in"))
    )
    (net (code "21") (name "Net-(IC5E-VDD18_VCO_SXT)") (class "Default")
      (node (ref "C247") (pin "1") (pinfunction "1_1") (pintype "passive"))
      (node (ref "FR90") (pin "1") (pinfunction "1_1") (pintype "passive"))
      (node (ref "IC5") (pin "G3") (pinfunction "VDD18_VCO_SXT_G3") (pintype "power_in"))
    )
    (net (code "22") (name "Net-(IC5F-DVDD_CGEN)") (class "Default")
      (node (ref "C202") (pin "1") (pinfunction "1_1") (pintype "passive"))
      (node (ref "C203") (pin "1") (pinfunction "1_1") (pintype "passive"))
      (node (ref "C204") (pin "1") (pinfunction "1_1") (pintype "passive"))
      (node (ref "FR69") (pin "1") (pinfunction "1_1") (pintype "passive"))
      (node (ref "IC5") (pin "A17") (pinfunction "DVDD_CGEN_A17") (pintype "power_in"))
      (node (ref "IC5") (pin "C25") (pinfunction "VDD12_DIG_C25") (pintype "power_in"))
      (node (ref "IC5") (pin "F24") (pinfunction "VDD_SPI_BUF_F24") (pintype "power_in"))
    )
    (net (code "23") (name "Net-(IC5F-DVDD_SXR)") (class "Default")
      (node (ref "C206") (pin "1") (pinfunction "1_1") (pintype "passive"))
      (node (ref "FR67") (pin "1") (pinfunction "1_1") (pintype "passive"))
      (node (ref "IC5") (pin "AL21") (pinfunction "DVDD_SXR_AL21") (pintype "power_in"))
    )
    (net (code "24") (name "Net-(IC5F-DVDD_SXT)") (class "Default")
      (node (ref "C205") (pin "2") (pinfunction "2_2") (pintype "passive"))
      (node (ref "FR68") (pin "1") (pinfunction "1_1") (pintype "passive"))
      (node (ref "IC5") (pin "M4") (pinfunction "DVDD_SXT_M4") (pintype "power_in"))
    )
    (net (code "25") (name "Net-(IC5F-VDD12O_VCO_SXT)") (class "Default")
      (node (ref "C227") (pin "2") (pinfunction "2_2") (pintype "passive"))
      (node (ref "FR70") (pin "1") (pinfunction "1_1") (pintype "passive"))
      (node (ref "IC5") (pin "J5") (pinfunction "VDD12O_VCO_SXT_J5") (pintype "power_in"))
      (node (ref "IC5") (pin "K6") (pinfunction "VDD12_VCO_SXT_K6") (pintype "power_in"))
    )
    (net (code "26") (name "Net-(IC5F-VDD12_LNA_RFE)") (class "Default")
      (node (ref "C224") (pin "1") (pinfunction "1_1") (pintype "passive"))
      (node (ref "FR74") (pin "1") (pinfunction "1_1") (pintype "passive"))
      (node (ref "IC5") (pin "AG5") (pinfunction "VDD12_LNA_RFE_AG5") (pintype "power_in"))
    )
    (net (code "27") (name "Net-(IC5F-VDD12_RXBUF)") (class "Default")
      (node (ref "C220") (pin "1") (pinfunction "1_1") (pintype "passive"))
      (node (ref "IC5") (pin "AP26") (pinfunction "VDD12_RXBUF_AP26") (pintype "power_in"))
      (node (ref "R102") (pin "1") (pinfunction "1_1") (pintype "passive"))
    )
    (net (code "28") (name "Net-(IC5F-VDD12_TIA_RFE)") (class "Default")
      (node (ref "C225") (pin "2") (pinfunction "2_2") (pintype "passive"))
      (node (ref "FR73") (pin "1") (pinfunction "1_1") (pintype "passive"))
      (node (ref "IC5") (pin "AD6") (pinfunction "VDD12_TIA_RFE_AD6") (pintype "power_in"))
    )
    (net (code "29") (name "Net-(IC5F-VDD12_TXBUF)") (class "Default")
      (node (ref "C213") (pin "1") (pinfunction "1_1") (pintype "passive"))
      (node (ref "IC5") (pin "G5") (pinfunction "VDD12_TXBUF_G5") (pintype "power_in"))
      (node (ref "R101") (pin "1") (pinfunction "1_1") (pintype "passive"))
    )
    (net (code "30") (name "Net-(IC5F-VDD12_VCO_SXR)") (class "Default")
      (node (ref "C221") (pin "1") (pinfunction "1_1") (pintype "passive"))
      (node (ref "FR77") (pin "1") (pinfunction "1_1") (pintype "passive"))
      (node (ref "IC5") (pin "AN23") (pinfunction "VDD12_VCO_SXR_AN23") (pintype "power_in"))
    )
    (net (code "31") (name "Net-(IC5F-VDD14_LNA_RFE)") (class "Default")
      (node (ref "C231") (pin "1") (pinfunction "1_1") (pintype "passive"))
      (node (ref "FR88") (pin "1") (pinfunction "1_1") (pintype "passive"))
      (node (ref "IC5") (pin "AF6") (pinfunction "VDD14_LNA_RFE_AF6") (pintype "power_in"))
    )
    (net (code "32") (name "Net-(IC5F-VDD14_RBB)") (class "Default")
      (node (ref "C233") (pin "1") (pinfunction "1_1") (pintype "passive"))
      (node (ref "FR86") (pin "1") (pinfunction "1_1") (pintype "passive"))
      (node (ref "IC5") (pin "AD4") (pinfunction "VDD14_RBB_AD4") (pintype "power_in"))
    )
    (net (code "33") (name "Net-(IC5F-VDD14_TIA_RFE)") (class "Default")
      (node (ref "C232") (pin "1") (pinfunction "1_1") (pintype "passive"))
      (node (ref "FR87") (pin "1") (pinfunction "1_1") (pintype "passive"))
      (node (ref "IC5") (pin "AF2") (pinfunction "VDD14_TIA_RFE_AF2") (pintype "power_in"))
    )
    (net (code "34") (name "Net-(IC5F-VDD14_VCO_CGEN)") (class "Default")
      (node (ref "C230") (pin "1") (pinfunction "1_1") (pintype "passive"))
      (node (ref "FR89") (pin "1") (pinfunction "1_1") (pintype "passive"))
      (node (ref "IC5") (pin "C21") (pinfunction "VDD14_VCO_CGEN_C21") (pintype "power_in"))
    )
    (net (code "35") (name "Net-(IC5F-VDDO_DIV_SXT)") (class "Default")
      (node (ref "C229") (pin "1") (pinfunction "1_1") (pintype "passive"))
      (node (ref "FR84") (pin "1") (pinfunction "1_1") (pintype "passive"))
      (node (ref "IC5") (pin "K2") (pinfunction "VDDO_DIV_SXT_K2") (pintype "power_in"))
      (node (ref "IC5") (pin "L5") (pinfunction "VDD_DIV_SXT_L5") (pintype "power_in"))
    )
    (net (code "36") (name "Net-(IC5F-VDDO_TLOBUF_TRF)") (class "Default")
      (node (ref "C215") (pin "1") (pinfunction "1_1") (pintype "passive"))
      (node (ref "FR83") (pin "1") (pinfunction "1_1") (pintype "passive"))
      (node (ref "IC5") (pin "D6") (pinfunction "VDDO_TLOBUF_TRF_D6") (pintype "power_in"))
      (node (ref "IC5") (pin "F8") (pinfunction "VDD_TLOBUF_TRF_F8") (pintype "power_in"))
    )
    (net (code "37") (name "Net-(IC5F-VDD_AFE)") (class "Default")
      (node (ref "C219") (pin "1") (pinfunction "1_1") (pintype "passive"))
      (node (ref "FR79") (pin "1") (pinfunction "1_1") (pintype "passive"))
      (node (ref "IC5") (pin "AJ25") (pinfunction "VDD_AFE_AJ25") (pintype "power_in"))
    )
    (net (code "38") (name "Net-(IC5F-VDD_CP_CGEN)") (class "Default")
      (node (ref "C218") (pin "2") (pinfunction "2_2") (pintype "passive"))
      (node (ref "FR80") (pin "1") (pinfunction "1_1") (pintype "passive"))
      (node (ref "IC5") (pin "F20") (pinfunction "VDD_CP_CGEN_F20") (pintype "power_in"))
    )
    (net (code "39") (name "Net-(IC5F-VDD_CP_SXR)") (class "Default")
      (node (ref "C223") (pin "1") (pinfunction "1_1") (pintype "passive"))
      (node (ref "FR75") (pin "1") (pinfunction "1_1") (pintype "passive"))
      (node (ref "IC5") (pin "AL19") (pinfunction "VDD_CP_SXR_AL19") (pintype "power_in"))
    )
    (net (code "40") (name "Net-(IC5F-VDD_CP_SXT)") (class "Default")
      (node (ref "C226") (pin "1") (pinfunction "1_1") (pintype "passive"))
      (node (ref "FR71") (pin "1") (pinfunction "1_1") (pintype "passive"))
      (node (ref "IC5") (pin "J3") (pinfunction "VDD_CP_SXT_J3") (pintype "power_in"))
    )
    (net (code "41") (name "Net-(IC5F-VDD_DIV_CGEN)") (class "Default")
      (node (ref "C217") (pin "1") (pinfunction "1_1") (pintype "passive"))
      (node (ref "FR81") (pin "1") (pinfunction "1_1") (pintype "passive"))
      (node (ref "IC5") (pin "E19") (pinfunction "VDD_DIV_CGEN_E19") (pintype "power_in"))
    )
    (net (code "42") (name "Net-(IC5F-VDD_DIV_SXR)") (class "Default")
      (node (ref "C222") (pin "1") (pinfunction "1_1") (pintype "passive"))
      (node (ref "FR76") (pin "1") (pinfunction "1_1") (pintype "passive"))
      (node (ref "IC5") (pin "AM20") (pinfunction "VDD_DIV_SXR_AM20") (pintype "power_in"))
    )
    (net (code "43") (name "Net-(IC5F-VDD_MXLOBUF_RFE)") (class "Default")
      (node (ref "C234") (pin "1") (pinfunction "1_1") (pintype "passive"))
      (node (ref "FR85") (pin "1") (pinfunction "1_1") (pintype "passive"))
      (node (ref "IC5") (pin "AN17") (pinfunction "VDD_MXLOBUF_RFE_AN17") (pintype "power_in"))
    )
    (net (code "44") (name "Net-(IC5F-VDD_TBB)") (class "Default")
      (node (ref "C214") (pin "1") (pinfunction "1_1") (pintype "passive"))
      (node (ref "FR72") (pin "1") (pinfunction "1_1") (pintype "passive"))
      (node (ref "IC5") (pin "P4") (pinfunction "VDD_TBB_P4") (pintype "power_in"))
    )
    (net (code "45") (name "Net-(IC5F-VDD_TPAD_TRF)") (class "Default")
      (node (ref "C216") (pin "1") (pinfunction "1_1") (pintype "passive"))
      (node (ref "FR82") (pin "1") (pinfunction "1_1") (pintype "passive"))
      (node (ref "IC5") (pin "B16") (pinfunction "VDD_TPAD_TRF_B16") (pintype "power_in"))
    )
    (net (code "46") (name "VCC1P4_LMS3") (class "Default")
      (node (ref "FR84") (pin "2") (pinfunction "2_2") (pintype "passive"))
      (node (ref "FR85") (pin "2") (pinfunction "2_2") (pintype "passive"))
      (node (ref "FR86") (pin "2") (pinfunction "2_2") (pintype "passive"))
      (node (ref "FR87") (pin "2") (pinfunction "2_2") (pintype "passive"))
      (node (ref "FR88") (pin "2") (pinfunction "2_2") (pintype "passive"))
      (node (ref "FR89") (pin "2") (pinfunction "2_2") (pintype "passive"))
      (node (ref "R99") (pin "1") (pinfunction "1_1") (pintype "passive"))
    )
    (net (code "47") (name "VCC1P8_LMS3") (class "Default")
      (node (ref "FR90") (pin "2") (pinfunction "2_2") (pintype "passive"))
      (node (ref "FR91") (pin "1") (pinfunction "1_1") (pintype "passive"))
      (node (ref "FR92") (pin "1") (pinfunction "1_1") (pintype "passive"))
      (node (ref "FR93") (pin "2") (pinfunction "2_2") (pintype "passive"))
      (node (ref "FR94") (pin "2") (pinfunction "2_2") (pintype "passive"))
      (node (ref "FR95") (pin "2") (pinfunction "2_2") (pintype "passive"))
      (node (ref "FR96") (pin "2") (pinfunction "2_2") (pintype "passive"))
      (node (ref "FR97") (pin "2") (pinfunction "2_2") (pintype "passive"))
      (node (ref "R103") (pin "2") (pinfunction "2_2") (pintype "passive"))
      (node (ref "R109") (pin "2") (pinfunction "2_2") (pintype "passive"))
      (node (ref "R110") (pin "1") (pinfunction "1_1") (pintype "passive"))
    )
    (net (code "48") (name "VCC1P25_LMS3") (class "Default")
      (node (ref "FR67") (pin "2") (pinfunction "2_2") (pintype "passive"))
      (node (ref "FR68") (pin "2") (pinfunction "2_2") (pintype "passive"))
      (node (ref "FR69") (pin "2") (pinfunction "2_2") (pintype "passive"))
      (node (ref "FR70") (pin "2") (pinfunction "2_2") (pintype "passive"))
      (node (ref "FR71") (pin "2") (pinfunction "2_2") (pintype "passive"))
      (node (ref "FR72") (pin "2") (pinfunction "2_2") (pintype "passive"))
      (node (ref "FR73") (pin "2") (pinfunction "2_2") (pintype "passive"))
      (node (ref "FR74") (pin "2") (pinfunction "2_2") (pintype "passive"))
      (node (ref "FR75") (pin "2") (pinfunction "2_2") (pintype "passive"))
      (node (ref "FR76") (pin "2") (pinfunction "2_2") (pintype "passive"))
      (node (ref "FR77") (pin "2") (pinfunction "2_2") (pintype "passive"))
      (node (ref "FR78") (pin "2") (pinfunction "2_2") (pintype "passive"))
      (node (ref "FR79") (pin "2") (pinfunction "2_2") (pintype "passive"))
      (node (ref "FR80") (pin "2") (pinfunction "2_2") (pintype "passive"))
      (node (ref "FR81") (pin "2") (pinfunction "2_2") (pintype "passive"))
      (node (ref "FR82") (pin "2") (pinfunction "2_2") (pintype "passive"))
      (node (ref "FR83") (pin "2") (pinfunction "2_2") (pintype "passive"))
      (node (ref "R100") (pin "1") (pinfunction "1_1") (pintype "passive"))
    )
    (net (code "49") (name "VDIO_LMS") (class "Default")
      (node (ref "C236") (pin "2") (pinfunction "2_2") (pintype "passive"))
      (node (ref "R104") (pin "1") (pinfunction "1_1") (pintype "passive"))
      (node (ref "R105") (pin "1") (pinfunction "1_1") (pintype "passive"))
      (node (ref "R106") (pin "1") (pinfunction "1_1") (pintype "passive"))
      (node (ref "R107") (pin "1") (pinfunction "1_1") (pintype "passive"))
      (node (ref "R108") (pin "1") (pinfunction "1_1") (pintype "passive"))
    )
  )
)
